# ovms_lilygo_tcall_pic.net
KiCad netlist of a schematic drawn in EAGLE
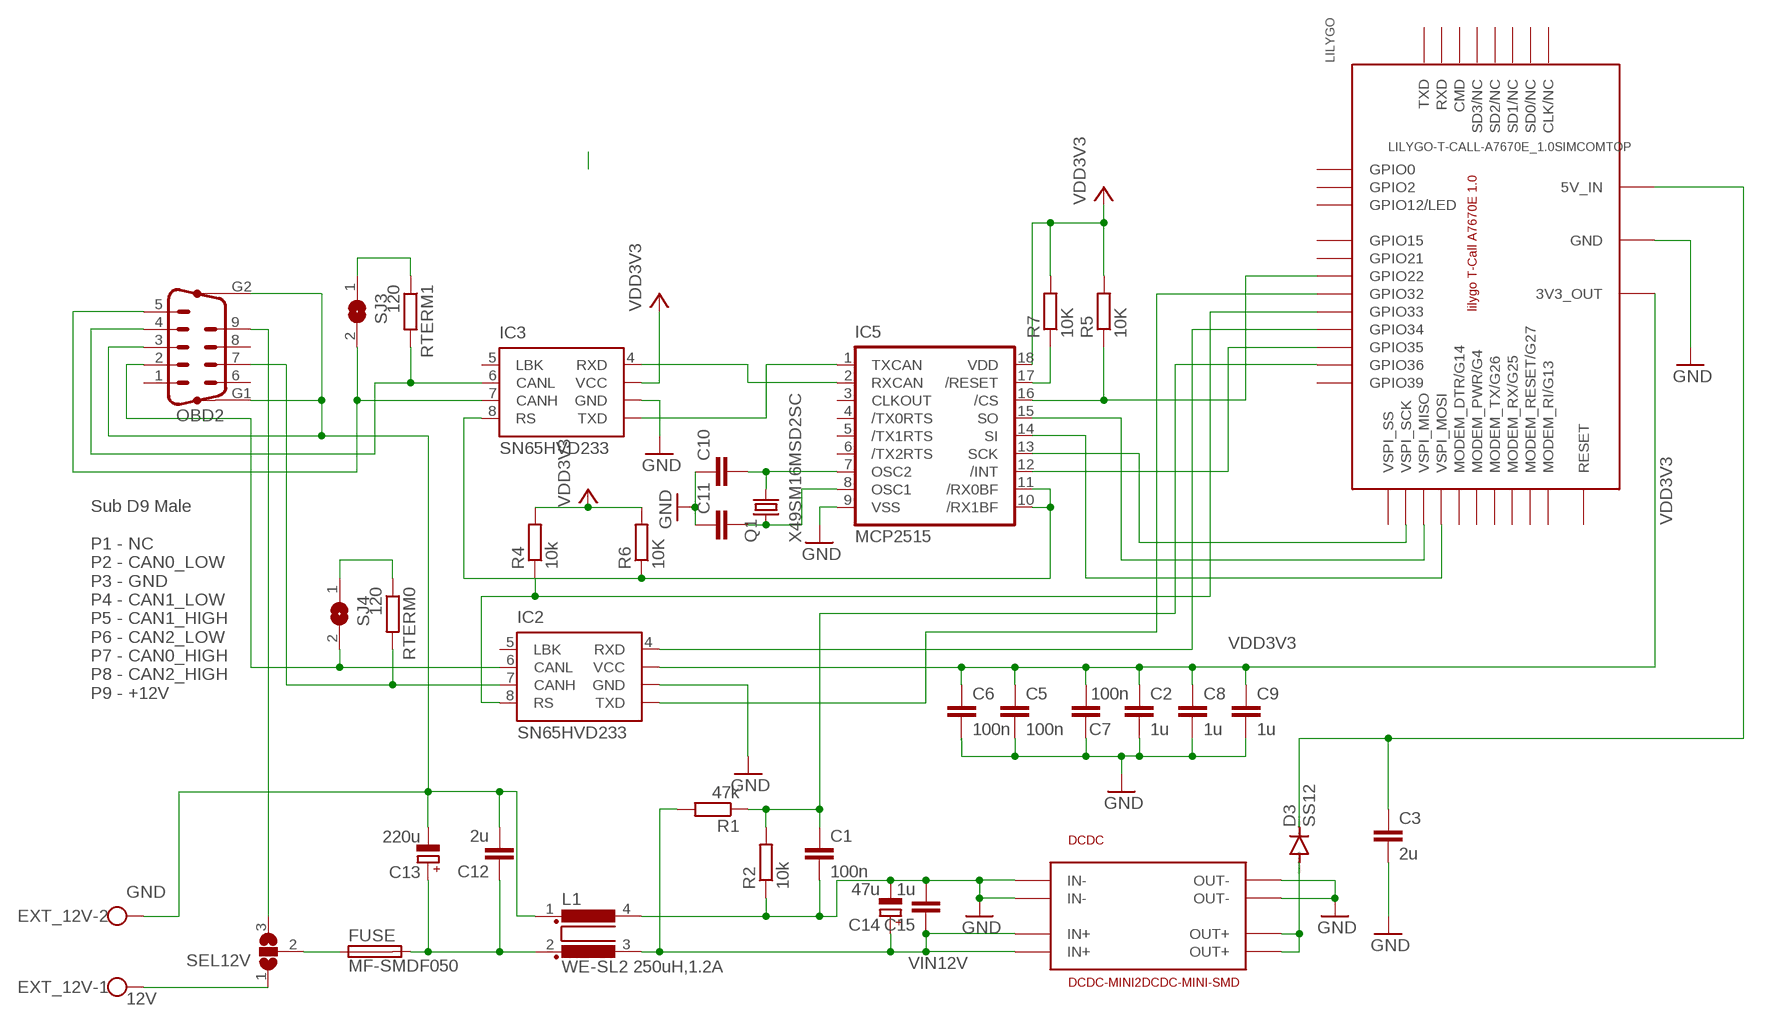
[diagram p0: schematic, sheet 1]

(export (version "E")
  (design (tool "Eeschema 10.0.6"))
  (components
    (comp (ref "C1")
      (value "100n")
      (footprint "eagle-import:C0805K")
      (libsource (lib "eagle-import") (part "C-EUC0805K"))
    )
    (comp (ref "C2")
      (value "1u")
      (footprint "eagle-import:C0805K")
      (libsource (lib "eagle-import") (part "C-EUC0805K"))
    )
    (comp (ref "C3")
      (value "2u")
      (footprint "eagle-import:C0805K")
      (libsource (lib "eagle-import") (part "C-EUC0805K"))
    )
    (comp (ref "C5")
      (value "100n")
      (footprint "eagle-import:C0805K")
      (libsource (lib "eagle-import") (part "C-EUC0805K"))
    )
    (comp (ref "C6")
      (value "100n")
      (footprint "eagle-import:C0805K")
      (libsource (lib "eagle-import") (part "C-EUC0805K"))
    )
    (comp (ref "C7")
      (value "100n")
      (footprint "eagle-import:C0805K")
      (libsource (lib "eagle-import") (part "C-EUC0805K"))
    )
    (comp (ref "C8")
      (value "1u")
      (footprint "eagle-import:C0805K")
      (libsource (lib "eagle-import") (part "C-EUC0805K"))
    )
    (comp (ref "C9")
      (value "1u")
      (footprint "eagle-import:C0805K")
      (libsource (lib "eagle-import") (part "C-EUC0805K"))
    )
    (comp (ref "C10")
      (value "22pF")
      (footprint "eagle-import:C0805K")
      (libsource (lib "eagle-import") (part "C-EUC0805K"))
    )
    (comp (ref "C11")
      (value "22pF")
      (footprint "eagle-import:C0805K")
      (libsource (lib "eagle-import") (part "C-EUC0805K"))
    )
    (comp (ref "C12")
      (value "2u")
      (footprint "eagle-import:C3216")
      (libsource (lib "eagle-import") (part "C-EUC3216"))
    )
    (comp (ref "C13")
      (value "220u")
      (footprint "eagle-import:UD-8X10_NICHICON")
      (libsource (lib "eagle-import") (part "CPOL-EUUD-8X10"))
    )
    (comp (ref "C14")
      (value "47u")
      (footprint "eagle-import:SMC_D")
      (libsource (lib "eagle-import") (part "CPOL-EUSMCD"))
    )
    (comp (ref "C15")
      (value "1u")
      (footprint "eagle-import:C3216")
      (libsource (lib "eagle-import") (part "C-EUC3216"))
    )
    (comp (ref "D3")
      (value "SS12")
      (footprint "eagle-import:SOD123")
      (libsource (lib "eagle-import") (part "DIODE-SOD123"))
    )
    (comp (ref "DCDC")
      (value "DCDC-MINI2DCDC-MINI-SMD")
      (footprint "eagle-import:DCDC-MINI-SMD")
      (libsource (lib "eagle-import") (part "DCDC-MINI2DCDC-MINI-SMD"))
    )
    (comp (ref "EXT_12V")
      (value "GND")
      (footprint "eagle-import:W237-102")
      (fields (field (name "MPN") "237-102") (field (name "VIN") "12V"))
      (libsource (lib "eagle-import") (part "W237-102"))
    )
    (comp (ref "FUSE")
      (value "MF-SMDF050")
      (footprint "eagle-import:MF-SMDF050")
      (libsource (lib "eagle-import") (part "MF-SMDF050"))
    )
    (comp (ref "IC2")
      (value "SN65HVD233")
      (footprint "eagle-import:SO-08")
      (libsource (lib "eagle-import") (part "SN65HVD23XS"))
    )
    (comp (ref "IC3")
      (value "SN65HVD233")
      (footprint "eagle-import:SO-08")
      (libsource (lib "eagle-import") (part "SN65HVD23XS"))
    )
    (comp (ref "IC5")
      (value "MCP2515")
      (footprint "eagle-import:SO-18W")
      (libsource (lib "eagle-import") (part "MCP2510S"))
    )
    (comp (ref "L1")
      (value "WE-SL2 250uH,1.2A")
      (footprint "eagle-import:CHOKE_SMD")
      (libsource (lib "eagle-import") (part "CM-CHOKE-SMD"))
    )
    (comp (ref "LILYGO")
      (value "LILYGO-T-CALL-A7670E_1.0SIMCOMTOP")
      (footprint "eagle-import:LILYGO-TCALL-A7670E_1.0")
      (libsource (lib "eagle-import") (part "LILYGO-T-CALL-A7670E_1.0SIMCOMTOP"))
    )
    (comp (ref "OBD2")
      (value "M09HP")
      (footprint "eagle-import:M09HP")
      (libsource (lib "eagle-import") (part "M09HP"))
    )
    (comp (ref "Q1")
      (value "X49SM16MSD2SC")
      (footprint "eagle-import:11.4X4.5")
      (libsource (lib "eagle-import") (part "KX-KS"))
    )
    (comp (ref "R1")
      (value "47k")
      (footprint "eagle-import:M0805")
      (libsource (lib "eagle-import") (part "R-EU_M0805"))
    )
    (comp (ref "R2")
      (value "10k")
      (footprint "eagle-import:M0805")
      (libsource (lib "eagle-import") (part "R-EU_M0805"))
    )
    (comp (ref "R4")
      (value "10k")
      (footprint "eagle-import:M0805")
      (libsource (lib "eagle-import") (part "R-EU_M0805"))
    )
    (comp (ref "R5")
      (value "10K")
      (footprint "eagle-import:M0805")
      (libsource (lib "eagle-import") (part "R-EU_M0805"))
    )
    (comp (ref "R6")
      (value "10K")
      (footprint "eagle-import:M0805")
      (libsource (lib "eagle-import") (part "R-EU_M0805"))
    )
    (comp (ref "R7")
      (value "10K")
      (footprint "eagle-import:M0805")
      (libsource (lib "eagle-import") (part "R-EU_M0805"))
    )
    (comp (ref "RTERM0")
      (value "120")
      (footprint "eagle-import:M0805")
      (libsource (lib "eagle-import") (part "R-EU_M0805"))
    )
    (comp (ref "RTERM1")
      (value "120")
      (footprint "eagle-import:M0805")
      (libsource (lib "eagle-import") (part "R-EU_M0805"))
    )
    (comp (ref "SEL12V")
      (value "SJ2W")
      (footprint "eagle-import:SJ_2")
      (libsource (lib "eagle-import") (part "SJ2W"))
    )
    (comp (ref "SJ3") (value "SJ") (footprint "eagle-import:SJ") (libsource (lib "eagle-import") (part "SJ")))
    (comp (ref "SJ4") (value "SJ") (footprint "eagle-import:SJ") (libsource (lib "eagle-import") (part "SJ")))
  )
  (nets
    (net (code "1") (name "/VIN12V") (class "Default")
      (node (ref "C14") (pin "+") (pinfunction "+_+") (pintype "passive"))
      (node (ref "C15") (pin "1") (pinfunction "1_1") (pintype "passive"))
      (node (ref "DCDC") (pin "IN+1") (pinfunction "IN+_IN+1") (pintype "power_in"))
      (node (ref "DCDC") (pin "IN+2") (pinfunction "IN+_IN+2") (pintype "power_in"))
      (node (ref "L1") (pin "3") (pinfunction "3_3") (pintype "passive"))
      (node (ref "R1") (pin "2") (pinfunction "2_2") (pintype "passive"))
    )
    (net (code "2") (name "GND") (class "Default")
      (node (ref "C1") (pin "2") (pinfunction "2_2") (pintype "passive"))
      (node (ref "C10") (pin "1") (pinfunction "1_1") (pintype "passive"))
      (node (ref "C11") (pin "1") (pinfunction "1_1") (pintype "passive"))
      (node (ref "C14") (pin "-") (pinfunction "-_-") (pintype "passive"))
      (node (ref "C15") (pin "2") (pinfunction "2_2") (pintype "passive"))
      (node (ref "C2") (pin "2") (pinfunction "2_2") (pintype "passive"))
      (node (ref "C3") (pin "2") (pinfunction "2_2") (pintype "passive"))
      (node (ref "C5") (pin "2") (pinfunction "2_2") (pintype "passive"))
      (node (ref "C6") (pin "2") (pinfunction "2_2") (pintype "passive"))
      (node (ref "C7") (pin "1") (pinfunction "1_1") (pintype "passive"))
      (node (ref "C8") (pin "2") (pinfunction "2_2") (pintype "passive"))
      (node (ref "C9") (pin "2") (pinfunction "2_2") (pintype "passive"))
      (node (ref "DCDC") (pin "IN-1") (pinfunction "IN-_IN-1") (pintype "power_in"))
      (node (ref "DCDC") (pin "IN-2") (pinfunction "IN-_IN-2") (pintype "power_in"))
      (node (ref "DCDC") (pin "OUT-1") (pinfunction "OUT-_OUT-1") (pintype "power_in"))
      (node (ref "DCDC") (pin "OUT-2") (pinfunction "OUT-_OUT-2") (pintype "power_in"))
      (node (ref "IC2") (pin "2") (pinfunction "GND_2") (pintype "power_in"))
      (node (ref "IC3") (pin "2") (pinfunction "GND_2") (pintype "power_in"))
      (node (ref "IC5") (pin "9") (pinfunction "VSS_9") (pintype "power_in"))
      (node (ref "L1") (pin "4") (pinfunction "4_4") (pintype "passive"))
      (node (ref "LILYGO") (pin "1") (pinfunction "GND_1") (pintype "bidirectional"))
      (node (ref "LILYGO") (pin "25") (pinfunction "GND_25") (pintype "bidirectional"))
      (node (ref "LILYGO") (pin "7") (pinfunction "GND_7") (pintype "bidirectional"))
      (node (ref "R2") (pin "1") (pinfunction "1_1") (pintype "passive"))
    )
    (net (code "3") (name "Net-(C12-Pad1)") (class "Default")
      (node (ref "C12") (pin "1") (pinfunction "1_1") (pintype "passive"))
      (node (ref "C13") (pin "+") (pinfunction "+_+") (pintype "passive"))
      (node (ref "FUSE") (pin "2") (pinfunction "2_2") (pintype "passive"))
      (node (ref "L1") (pin "2") (pinfunction "2_2") (pintype "passive"))
    )
    (net (code "4") (name "Net-(D3-PadA)") (class "Default")
      (node (ref "D3") (pin "A") (pinfunction "A_A") (pintype "passive"))
      (node (ref "DCDC") (pin "OUT+1") (pinfunction "OUT+_OUT+1") (pintype "power_in"))
      (node (ref "DCDC") (pin "OUT+2") (pinfunction "OUT+_OUT+2") (pintype "power_in"))
    )
    (net (code "5") (name "Net-(EXT_12VA-KL)") (class "Default")
      (node (ref "EXT_12V") (pin "1") (pinfunction "KL_1") (pintype "passive"))
      (node (ref "SEL12V") (pin "1") (pinfunction "1_1") (pintype "passive"))
    )
    (net (code "6") (name "Net-(EXT_12VB-KL)") (class "Default")
      (node (ref "C12") (pin "2") (pinfunction "2_2") (pintype "passive"))
      (node (ref "C13") (pin "-") (pinfunction "-_-") (pintype "passive"))
      (node (ref "EXT_12V") (pin "2") (pinfunction "KL_2") (pintype "passive"))
      (node (ref "L1") (pin "1") (pinfunction "1_1") (pintype "passive"))
      (node (ref "OBD2") (pin "3") (pinfunction "3_3") (pintype "passive"))
      (node (ref "OBD2") (pin "G1") (pinfunction "G1_G1") (pintype "passive"))
      (node (ref "OBD2") (pin "G2") (pinfunction "G2_G2") (pintype "passive"))
    )
    (net (code "7") (name "Net-(FUSE-Pad1)") (class "Default")
      (node (ref "FUSE") (pin "1") (pinfunction "1_1") (pintype "passive"))
      (node (ref "SEL12V") (pin "2") (pinfunction "2_2") (pintype "passive"))
    )
    (net (code "8") (name "Net-(IC2-CANH)") (class "Default")
      (node (ref "IC2") (pin "7") (pinfunction "CANH_7") (pintype "input"))
      (node (ref "OBD2") (pin "7") (pinfunction "7_7") (pintype "passive"))
      (node (ref "RTERM0") (pin "2") (pinfunction "2_2") (pintype "passive"))
    )
    (net (code "9") (name "Net-(IC2-CANL)") (class "Default")
      (node (ref "IC2") (pin "6") (pinfunction "CANL_6") (pintype "input"))
      (node (ref "OBD2") (pin "2") (pinfunction "2_2") (pintype "passive"))
      (node (ref "SJ4") (pin "2") (pinfunction "2_2") (pintype "passive"))
    )
    (net (code "10") (name "Net-(IC2-RS)") (class "Default")
      (node (ref "IC2") (pin "8") (pinfunction "RS_8") (pintype "input"))
      (node (ref "LILYGO") (pin "31") (pinfunction "GPIO33_31") (pintype "bidirectional"))
      (node (ref "R4") (pin "1") (pinfunction "1_1") (pintype "passive"))
    )
    (net (code "11") (name "Net-(IC2-RXD)") (class "Default")
      (node (ref "IC2") (pin "4") (pinfunction "RXD_4") (pintype "input"))
      (node (ref "LILYGO") (pin "34") (pinfunction "GPIO34_34") (pintype "bidirectional"))
    )
    (net (code "12") (name "Net-(IC2-TXD)") (class "Default")
      (node (ref "IC2") (pin "1") (pinfunction "TXD_1") (pintype "bidirectional"))
      (node (ref "LILYGO") (pin "32") (pinfunction "GPIO32_32") (pintype "bidirectional"))
    )
    (net (code "13") (name "Net-(IC3-CANH)") (class "Default")
      (node (ref "IC3") (pin "7") (pinfunction "CANH_7") (pintype "input"))
      (node (ref "OBD2") (pin "5") (pinfunction "5_5") (pintype "passive"))
      (node (ref "SJ3") (pin "2") (pinfunction "2_2") (pintype "passive"))
    )
    (net (code "14") (name "Net-(IC3-CANL)") (class "Default")
      (node (ref "IC3") (pin "6") (pinfunction "CANL_6") (pintype "input"))
      (node (ref "OBD2") (pin "4") (pinfunction "4_4") (pintype "passive"))
      (node (ref "RTERM1") (pin "2") (pinfunction "2_2") (pintype "passive"))
    )
    (net (code "15") (name "Net-(IC3-RS)") (class "Default")
      (node (ref "IC3") (pin "8") (pinfunction "RS_8") (pintype "input"))
      (node (ref "IC5") (pin "10") (pinfunction "/RX1BF_10") (pintype "bidirectional"))
      (node (ref "IC5") (pin "11") (pinfunction "/RX0BF_11") (pintype "bidirectional"))
      (node (ref "R6") (pin "1") (pinfunction "1_1") (pintype "passive"))
    )
    (net (code "16") (name "Net-(IC3-RXD)") (class "Default")
      (node (ref "IC3") (pin "4") (pinfunction "RXD_4") (pintype "input"))
      (node (ref "IC5") (pin "2") (pinfunction "RXCAN_2") (pintype "bidirectional"))
    )
    (net (code "17") (name "Net-(IC3-TXD)") (class "Default")
      (node (ref "IC3") (pin "1") (pinfunction "TXD_1") (pintype "bidirectional"))
      (node (ref "IC5") (pin "1") (pinfunction "TXCAN_1") (pintype "input"))
    )
    (net (code "18") (name "Net-(IC5-OSC1)") (class "Default")
      (node (ref "C11") (pin "2") (pinfunction "2_2") (pintype "passive"))
      (node (ref "IC5") (pin "8") (pinfunction "OSC1_8") (pintype "input"))
      (node (ref "Q1") (pin "1") (pinfunction "1_1") (pintype "passive"))
    )
    (net (code "19") (name "Net-(IC5-OSC2)") (class "Default")
      (node (ref "C10") (pin "2") (pinfunction "2_2") (pintype "passive"))
      (node (ref "IC5") (pin "7") (pinfunction "OSC2_7") (pintype "output"))
      (node (ref "Q1") (pin "2") (pinfunction "2_2") (pintype "passive"))
    )
    (net (code "20") (name "Net-(IC5-SCK)") (class "Default")
      (node (ref "IC5") (pin "13") (pinfunction "SCK_13") (pintype "bidirectional"))
      (node (ref "LILYGO") (pin "9") (pinfunction "VSPI_SCK_9") (pintype "output"))
    )
    (net (code "21") (name "Net-(IC5-SI)") (class "Default")
      (node (ref "IC5") (pin "14") (pinfunction "SI_14") (pintype "bidirectional"))
      (node (ref "LILYGO") (pin "2") (pinfunction "VSPI_MOSI_2") (pintype "bidirectional"))
    )
    (net (code "22") (name "Net-(IC5-SO)") (class "Default")
      (node (ref "IC5") (pin "15") (pinfunction "SO_15") (pintype "bidirectional"))
      (node (ref "LILYGO") (pin "8") (pinfunction "VSPI_MISO_8") (pintype "bidirectional"))
    )
    (net (code "23") (name "Net-(IC5-{slash}CS)") (class "Default")
      (node (ref "IC5") (pin "16") (pinfunction "/CS_16") (pintype "bidirectional"))
      (node (ref "LILYGO") (pin "3") (pinfunction "GPIO22_3") (pintype "output"))
      (node (ref "R5") (pin "1") (pinfunction "1_1") (pintype "passive"))
    )
    (net (code "24") (name "Net-(IC5-{slash}INT)") (class "Default")
      (node (ref "IC5") (pin "12") (pinfunction "/INT_12") (pintype "bidirectional"))
      (node (ref "LILYGO") (pin "33") (pinfunction "GPIO35_33") (pintype "bidirectional"))
    )
    (net (code "25") (name "Net-(IC5-{slash}RESET)") (class "Default")
      (node (ref "IC5") (pin "17") (pinfunction "/RESET_17") (pintype "bidirectional"))
      (node (ref "R7") (pin "1") (pinfunction "1_1") (pintype "passive"))
    )
    (net (code "26") (name "Net-(LILYGO-5V_IN)") (class "Default")
      (node (ref "C3") (pin "1") (pinfunction "1_1") (pintype "passive"))
      (node (ref "D3") (pin "C") (pinfunction "C_C") (pintype "passive"))
      (node (ref "LILYGO") (pin "20") (pinfunction "5V_IN_20") (pintype "power_in"))
    )
    (net (code "27") (name "Net-(LILYGO-GPIO36)") (class "Default")
      (node (ref "C1") (pin "1") (pinfunction "1_1") (pintype "passive"))
      (node (ref "LILYGO") (pin "36") (pinfunction "GPIO36_36") (pintype "bidirectional"))
      (node (ref "R1") (pin "1") (pinfunction "1_1") (pintype "passive"))
      (node (ref "R2") (pin "2") (pinfunction "2_2") (pintype "passive"))
    )
    (net (code "28") (name "Net-(OBD2-Pad9)") (class "Default")
      (node (ref "OBD2") (pin "9") (pinfunction "9_9") (pintype "passive"))
      (node (ref "SEL12V") (pin "3") (pinfunction "3_3") (pintype "passive"))
    )
    (net (code "29") (name "Net-(RTERM0-Pad1)") (class "Default")
      (node (ref "RTERM0") (pin "1") (pinfunction "1_1") (pintype "passive"))
      (node (ref "SJ4") (pin "1") (pinfunction "1_1") (pintype "passive"))
    )
    (net (code "30") (name "Net-(RTERM1-Pad1)") (class "Default")
      (node (ref "RTERM1") (pin "1") (pinfunction "1_1") (pintype "passive"))
      (node (ref "SJ3") (pin "1") (pinfunction "1_1") (pintype "passive"))
    )
    (net (code "31") (name "VDD3V3") (class "Default")
      (node (ref "C2") (pin "1") (pinfunction "1_1") (pintype "passive"))
      (node (ref "C5") (pin "1") (pinfunction "1_1") (pintype "passive"))
      (node (ref "C6") (pin "1") (pinfunction "1_1") (pintype "passive"))
      (node (ref "C7") (pin "2") (pinfunction "2_2") (pintype "passive"))
      (node (ref "C8") (pin "1") (pinfunction "1_1") (pintype "passive"))
      (node (ref "C9") (pin "1") (pinfunction "1_1") (pintype "passive"))
      (node (ref "IC2") (pin "3") (pinfunction "VCC_3") (pintype "power_in"))
      (node (ref "IC3") (pin "3") (pinfunction "VCC_3") (pintype "power_in"))
      (node (ref "IC5") (pin "18") (pinfunction "VDD_18") (pintype "power_in"))
      (node (ref "LILYGO") (pin "38") (pinfunction "3V3_OUT_38") (pintype "output"))
      (node (ref "R4") (pin "2") (pinfunction "2_2") (pintype "passive"))
      (node (ref "R5") (pin "2") (pinfunction "2_2") (pintype "passive"))
      (node (ref "R6") (pin "2") (pinfunction "2_2") (pintype "passive"))
      (node (ref "R7") (pin "2") (pinfunction "2_2") (pintype "passive"))
    )
    (net (code "32") (name "unconnected-(IC2-LBK-Pad5)") (class "Default")
      (node (ref "IC2") (pin "5") (pinfunction "LBK_5") (pintype "input"))
    )
    (net (code "33") (name "unconnected-(IC3-LBK-Pad5)") (class "Default")
      (node (ref "IC3") (pin "5") (pinfunction "LBK_5") (pintype "input"))
    )
    (net (code "34") (name "unconnected-(IC5-CLKOUT-Pad3)") (class "Default")
      (node (ref "IC5") (pin "3") (pinfunction "CLKOUT_3") (pintype "bidirectional"))
    )
    (net (code "35") (name "unconnected-(IC5-{slash}TX0RTS-Pad4)") (class "Default")
      (node (ref "IC5") (pin "4") (pinfunction "/TX0RTS_4") (pintype "bidirectional"))
    )
    (net (code "36") (name "unconnected-(IC5-{slash}TX1RTS-Pad5)") (class "Default")
      (node (ref "IC5") (pin "5") (pinfunction "/TX1RTS_5") (pintype "bidirectional"))
    )
    (net (code "37") (name "unconnected-(IC5-{slash}TX2RTS-Pad6)") (class "Default")
      (node (ref "IC5") (pin "6") (pinfunction "/TX2RTS_6") (pintype "input"))
    )
    (net (code "38") (name "unconnected-(LILYGO-CLK{slash}NC-Pad19)") (class "Default")
      (node (ref "LILYGO") (pin "19") (pinfunction "CLK/NC_19") (pintype "output"))
    )
    (net (code "39") (name "unconnected-(LILYGO-CMD-Pad21)") (class "Default")
      (node (ref "LILYGO") (pin "21") (pinfunction "CMD_21") (pintype "bidirectional"))
    )
    (net (code "40") (name "unconnected-(LILYGO-GPIO0-Pad14)") (class "Default")
      (node (ref "LILYGO") (pin "14") (pinfunction "GPIO0_14") (pintype "bidirectional"))
    )
    (net (code "41") (name "unconnected-(LILYGO-GPIO2-Pad15)") (class "Default")
      (node (ref "LILYGO") (pin "15") (pinfunction "GPIO2_15") (pintype "bidirectional"))
    )
    (net (code "42") (name "unconnected-(LILYGO-GPIO12{slash}LED-Pad26)") (class "Default")
      (node (ref "LILYGO") (pin "26") (pinfunction "GPIO12/LED_26") (pintype "bidirectional"))
    )
    (net (code "43") (name "unconnected-(LILYGO-GPIO15-Pad16)") (class "Default")
      (node (ref "LILYGO") (pin "16") (pinfunction "GPIO15_16") (pintype "bidirectional"))
    )
    (net (code "44") (name "unconnected-(LILYGO-GPIO21-Pad6)") (class "Default")
      (node (ref "LILYGO") (pin "6") (pinfunction "GPIO21_6") (pintype "bidirectional"))
    )
    (net (code "45") (name "unconnected-(LILYGO-GPIO39-Pad35)") (class "Default")
      (node (ref "LILYGO") (pin "35") (pinfunction "GPIO39_35") (pintype "bidirectional"))
    )
    (net (code "46") (name "unconnected-(LILYGO-MODEM_DTR{slash}G14-Pad27)") (class "Default")
      (node (ref "LILYGO") (pin "27") (pinfunction "MODEM_DTR/G14_27") (pintype "bidirectional"))
    )
    (net (code "47") (name "unconnected-(LILYGO-MODEM_PWR{slash}G4-Pad13)") (class "Default")
      (node (ref "LILYGO") (pin "13") (pinfunction "MODEM_PWR/G4_13") (pintype "output"))
    )
    (net (code "48") (name "unconnected-(LILYGO-MODEM_RESET{slash}G27-Pad28)") (class "Default")
      (node (ref "LILYGO") (pin "28") (pinfunction "MODEM_RESET/G27_28") (pintype "output"))
    )
    (net (code "49") (name "unconnected-(LILYGO-MODEM_RI{slash}G13-Pad24)") (class "Default")
      (node (ref "LILYGO") (pin "24") (pinfunction "MODEM_RI/G13_24") (pintype "output"))
    )
    (net (code "50") (name "unconnected-(LILYGO-MODEM_RX{slash}G25-Pad30)") (class "Default")
      (node (ref "LILYGO") (pin "30") (pinfunction "MODEM_RX/G25_30") (pintype "output"))
    )
    (net (code "51") (name "unconnected-(LILYGO-MODEM_TX{slash}G26-Pad29)") (class "Default")
      (node (ref "LILYGO") (pin "29") (pinfunction "MODEM_TX/G26_29") (pintype "output"))
    )
    (net (code "52") (name "unconnected-(LILYGO-RESET-Pad37)") (class "Default")
      (node (ref "LILYGO") (pin "37") (pinfunction "RESET_37") (pintype "input"))
    )
    (net (code "53") (name "unconnected-(LILYGO-RXD-Pad5)") (class "Default")
      (node (ref "LILYGO") (pin "5") (pinfunction "RXD_5") (pintype "input"))
    )
    (net (code "54") (name "unconnected-(LILYGO-SD0{slash}NC-Pad18)") (class "Default")
      (node (ref "LILYGO") (pin "18") (pinfunction "SD0/NC_18") (pintype "output"))
    )
    (net (code "55") (name "unconnected-(LILYGO-SD1{slash}NC-Pad17)") (class "Default")
      (node (ref "LILYGO") (pin "17") (pinfunction "SD1/NC_17") (pintype "output"))
    )
    (net (code "56") (name "unconnected-(LILYGO-SD2{slash}NC-Pad23)") (class "Default")
      (node (ref "LILYGO") (pin "23") (pinfunction "SD2/NC_23") (pintype "bidirectional"))
    )
    (net (code "57") (name "unconnected-(LILYGO-SD3{slash}NC-Pad22)") (class "Default")
      (node (ref "LILYGO") (pin "22") (pinfunction "SD3/NC_22") (pintype "output"))
    )
    (net (code "58") (name "unconnected-(LILYGO-TXD-Pad4)") (class "Default")
      (node (ref "LILYGO") (pin "4") (pinfunction "TXD_4") (pintype "output"))
    )
    (net (code "59") (name "unconnected-(LILYGO-VSPI_SS-Pad10)") (class "Default")
      (node (ref "LILYGO") (pin "10") (pinfunction "VSPI_SS_10") (pintype "bidirectional"))
    )
    (net (code "60") (name "unconnected-(OBD2-Pad1)") (class "Default")
      (node (ref "OBD2") (pin "1") (pinfunction "1_1") (pintype "passive"))
    )
    (net (code "61") (name "unconnected-(OBD2-Pad6)") (class "Default")
      (node (ref "OBD2") (pin "6") (pinfunction "6_6") (pintype "passive"))
    )
    (net (code "62") (name "unconnected-(OBD2-Pad8)") (class "Default")
      (node (ref "OBD2") (pin "8") (pinfunction "8_8") (pintype "passive"))
    )
  )
)
